# lab4.net
KiCad netlist of a schematic drawn in EAGLE
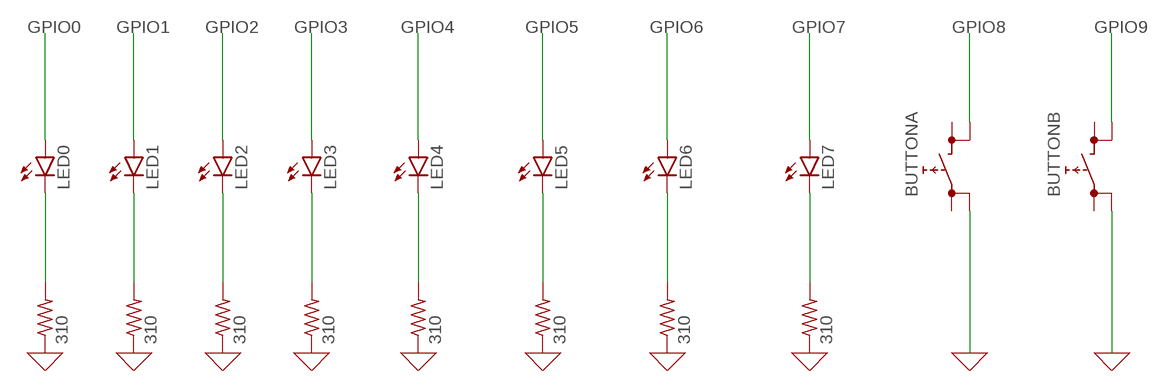
[diagram p0: schematic, sheet 1]

(export (version "E")
  (design (tool "Eeschema 10.0.6"))
  (components
    (comp (ref "BUTTONA")
      (value "REKN")
      (footprint "eagle-import:REKN")
      (libsource (lib "eagle-import") (part "REKN"))
    )
    (comp (ref "BUTTONB")
      (value "REKN")
      (footprint "eagle-import:REKN")
      (libsource (lib "eagle-import") (part "REKN"))
    )
    (comp (ref "LED0")
      (value "LAP4-BOTTOM")
      (footprint "eagle-import:P47F-BOTTOM")
      (libsource (lib "eagle-import") (part "P4-BOTTOMLA"))
    )
    (comp (ref "LED1")
      (value "LAP4-BOTTOM")
      (footprint "eagle-import:P47F-BOTTOM")
      (libsource (lib "eagle-import") (part "P4-BOTTOMLA"))
    )
    (comp (ref "LED2")
      (value "LAP4-BOTTOM")
      (footprint "eagle-import:P47F-BOTTOM")
      (libsource (lib "eagle-import") (part "P4-BOTTOMLA"))
    )
    (comp (ref "LED3")
      (value "LAP4-BOTTOM")
      (footprint "eagle-import:P47F-BOTTOM")
      (libsource (lib "eagle-import") (part "P4-BOTTOMLA"))
    )
    (comp (ref "LED4")
      (value "LAP4-BOTTOM")
      (footprint "eagle-import:P47F-BOTTOM")
      (libsource (lib "eagle-import") (part "P4-BOTTOMLA"))
    )
    (comp (ref "LED5")
      (value "LAP4-BOTTOM")
      (footprint "eagle-import:P47F-BOTTOM")
      (libsource (lib "eagle-import") (part "P4-BOTTOMLA"))
    )
    (comp (ref "LED6")
      (value "LAP4-BOTTOM")
      (footprint "eagle-import:P47F-BOTTOM")
      (libsource (lib "eagle-import") (part "P4-BOTTOMLA"))
    )
    (comp (ref "LED7")
      (value "LAP4-BOTTOM")
      (footprint "eagle-import:P47F-BOTTOM")
      (libsource (lib "eagle-import") (part "P4-BOTTOMLA"))
    )
    (comp (ref "R1")
      (value "310")
      (footprint "eagle-import:0204V")
      (libsource (lib "eagle-import") (part "R-US_0204/2V"))
    )
    (comp (ref "R2")
      (value "310")
      (footprint "eagle-import:0204V")
      (libsource (lib "eagle-import") (part "R-US_0204/2V"))
    )
    (comp (ref "R3")
      (value "310")
      (footprint "eagle-import:0204V")
      (libsource (lib "eagle-import") (part "R-US_0204/2V"))
    )
    (comp (ref "R4")
      (value "310")
      (footprint "eagle-import:0204V")
      (libsource (lib "eagle-import") (part "R-US_0204/2V"))
    )
    (comp (ref "R5")
      (value "310")
      (footprint "eagle-import:0204V")
      (libsource (lib "eagle-import") (part "R-US_0204/2V"))
    )
    (comp (ref "R6")
      (value "310")
      (footprint "eagle-import:0204V")
      (libsource (lib "eagle-import") (part "R-US_0204/2V"))
    )
    (comp (ref "R7")
      (value "310")
      (footprint "eagle-import:0204V")
      (libsource (lib "eagle-import") (part "R-US_0204/2V"))
    )
    (comp (ref "R8")
      (value "310")
      (footprint "eagle-import:0204V")
      (libsource (lib "eagle-import") (part "R-US_0204/2V"))
    )
  )
  (nets
    (net (code "1") (name "/GPIO0") (class "Default")
      (node (ref "LED0") (pin "A") (pinfunction "A_A") (pintype "passive"))
    )
    (net (code "2") (name "/GPIO1") (class "Default")
      (node (ref "LED1") (pin "A") (pinfunction "A_A") (pintype "passive"))
    )
    (net (code "3") (name "/GPIO2") (class "Default")
      (node (ref "LED2") (pin "A") (pinfunction "A_A") (pintype "passive"))
    )
    (net (code "4") (name "/GPIO3") (class "Default")
      (node (ref "LED3") (pin "A") (pinfunction "A_A") (pintype "passive"))
    )
    (net (code "5") (name "/GPIO4") (class "Default")
      (node (ref "LED4") (pin "A") (pinfunction "A_A") (pintype "passive"))
    )
    (net (code "6") (name "/GPIO5") (class "Default")
      (node (ref "LED5") (pin "A") (pinfunction "A_A") (pintype "passive"))
    )
    (net (code "7") (name "/GPIO6") (class "Default")
      (node (ref "LED6") (pin "A") (pinfunction "A_A") (pintype "passive"))
    )
    (net (code "8") (name "/GPIO7") (class "Default")
      (node (ref "LED7") (pin "A") (pinfunction "A_A") (pintype "passive"))
    )
    (net (code "9") (name "/GPIO8") (class "Default")
      (node (ref "BUTTONA") (pin "1B") (pinfunction "1_1B") (pintype "passive"))
    )
    (net (code "10") (name "/GPIO9") (class "Default")
      (node (ref "BUTTONB") (pin "1B") (pinfunction "1_1B") (pintype "passive"))
    )
    (net (code "11") (name "GND") (class "Default")
      (node (ref "BUTTONA") (pin "0B") (pinfunction "0_0B") (pintype "passive"))
      (node (ref "BUTTONB") (pin "0B") (pinfunction "0_0B") (pintype "passive"))
      (node (ref "R1") (pin "1") (pinfunction "1_1") (pintype "passive"))
      (node (ref "R2") (pin "1") (pinfunction "1_1") (pintype "passive"))
      (node (ref "R3") (pin "1") (pinfunction "1_1") (pintype "passive"))
      (node (ref "R4") (pin "1") (pinfunction "1_1") (pintype "passive"))
      (node (ref "R5") (pin "1") (pinfunction "1_1") (pintype "passive"))
      (node (ref "R6") (pin "1") (pinfunction "1_1") (pintype "passive"))
      (node (ref "R7") (pin "1") (pinfunction "1_1") (pintype "passive"))
      (node (ref "R8") (pin "1") (pinfunction "1_1") (pintype "passive"))
    )
    (net (code "12") (name "Net-(LED0-PadC)") (class "Default")
      (node (ref "LED0") (pin "C") (pinfunction "C_C") (pintype "passive"))
      (node (ref "R7") (pin "2") (pinfunction "2_2") (pintype "passive"))
    )
    (net (code "13") (name "Net-(LED1-PadC)") (class "Default")
      (node (ref "LED1") (pin "C") (pinfunction "C_C") (pintype "passive"))
      (node (ref "R6") (pin "2") (pinfunction "2_2") (pintype "passive"))
    )
    (net (code "14") (name "Net-(LED2-PadC)") (class "Default")
      (node (ref "LED2") (pin "C") (pinfunction "C_C") (pintype "passive"))
      (node (ref "R5") (pin "2") (pinfunction "2_2") (pintype "passive"))
    )
    (net (code "15") (name "Net-(LED3-PadC)") (class "Default")
      (node (ref "LED3") (pin "C") (pinfunction "C_C") (pintype "passive"))
      (node (ref "R4") (pin "2") (pinfunction "2_2") (pintype "passive"))
    )
    (net (code "16") (name "Net-(LED4-PadC)") (class "Default")
      (node (ref "LED4") (pin "C") (pinfunction "C_C") (pintype "passive"))
      (node (ref "R1") (pin "2") (pinfunction "2_2") (pintype "passive"))
    )
    (net (code "17") (name "Net-(LED5-PadC)") (class "Default")
      (node (ref "LED5") (pin "C") (pinfunction "C_C") (pintype "passive"))
      (node (ref "R2") (pin "2") (pinfunction "2_2") (pintype "passive"))
    )
    (net (code "18") (name "Net-(LED6-PadC)") (class "Default")
      (node (ref "LED6") (pin "C") (pinfunction "C_C") (pintype "passive"))
      (node (ref "R3") (pin "2") (pinfunction "2_2") (pintype "passive"))
    )
    (net (code "19") (name "Net-(LED7-PadC)") (class "Default")
      (node (ref "LED7") (pin "C") (pinfunction "C_C") (pintype "passive"))
      (node (ref "R8") (pin "2") (pinfunction "2_2") (pintype "passive"))
    )
    (net (code "20") (name "unconnected-(BUTTONA-0-Pad0A)") (class "Default")
      (node (ref "BUTTONA") (pin "0A") (pinfunction "0_0A") (pintype "passive"))
    )
    (net (code "21") (name "unconnected-(BUTTONA-1-Pad1A)") (class "Default")
      (node (ref "BUTTONA") (pin "1A") (pinfunction "1_1A") (pintype "passive"))
    )
    (net (code "22") (name "unconnected-(BUTTONB-0-Pad0A)") (class "Default")
      (node (ref "BUTTONB") (pin "0A") (pinfunction "0_0A") (pintype "passive"))
    )
    (net (code "23") (name "unconnected-(BUTTONB-1-Pad1A)") (class "Default")
      (node (ref "BUTTONB") (pin "1A") (pinfunction "1_1A") (pintype "passive"))
    )
  )
)
